# eurorack-passive-hpeq.net
KiCad netlist of a schematic drawn in EAGLE
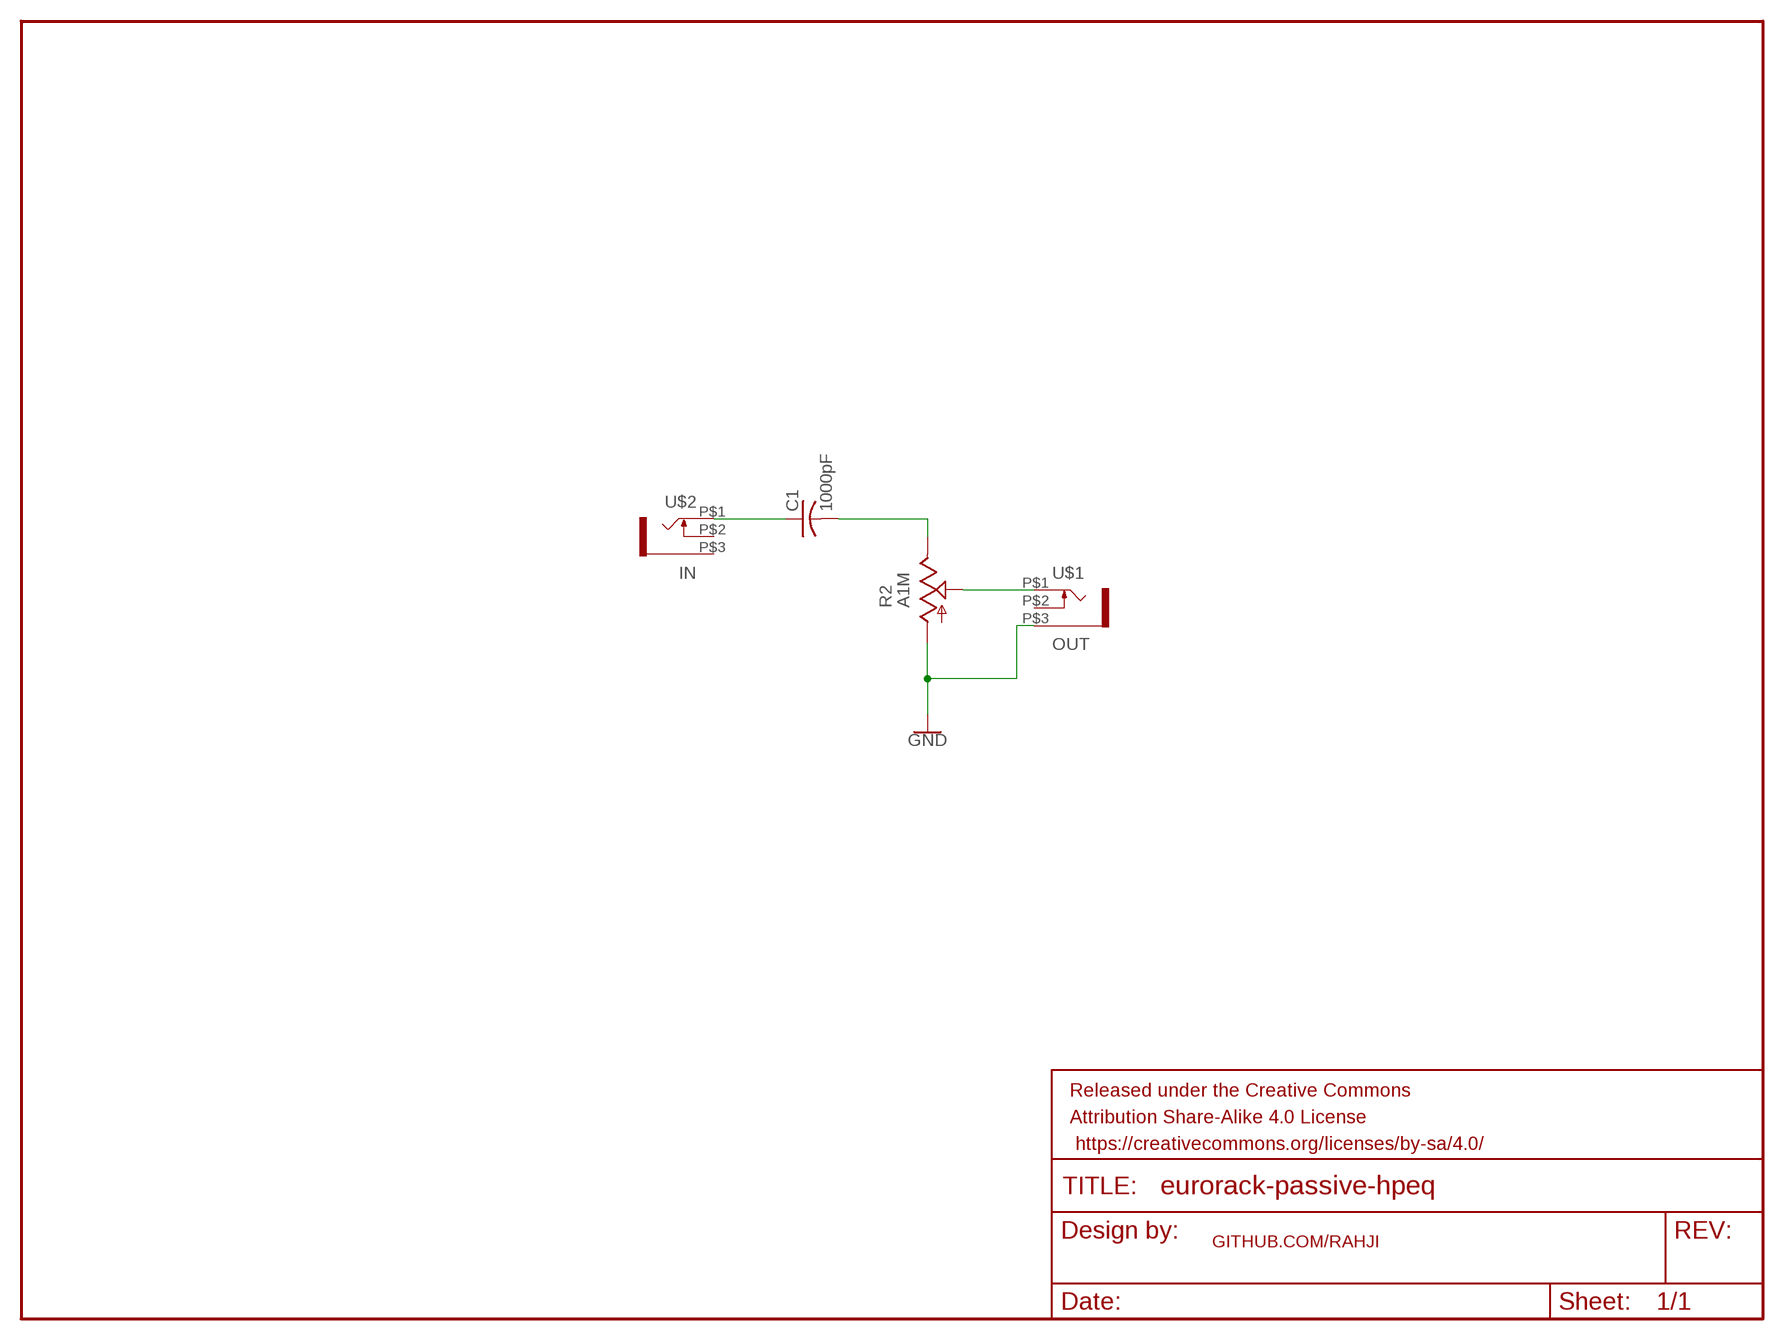
[diagram p0: schematic, sheet 1]

(export (version "E")
  (design (tool "Eeschema 10.0.6"))
  (components
    (comp (ref "C1")
      (value "1000pF")
      (footprint "eagle-import:C025-025X050")
      (libsource (lib "eagle-import") (part "C-US025-025X050"))
    )
    (comp (ref "FRAME1")
      (value "FRAME-LETTERNO_PACKAGE")
      (footprint "eagle-import:DUMMY")
      (fields (field (name "DESIGNER") "Nobody"))
      (libsource (lib "eagle-import") (part "FRAME-LETTERNO_PACKAGE"))
    )
    (comp (ref "R2")
      (value "A1M")
      (footprint "eagle-import:EVUF")
      (libsource (lib "eagle-import") (part "ALPHA-9MMAF3"))
    )
    (comp (ref "U$1")
      (value "OUT")
      (footprint "eagle-import:WQP-PJ301M-12_JACK")
      (libsource (lib "eagle-import") (part "WQP-PJ301M-12_JACK"))
    )
    (comp (ref "U$2")
      (value "IN")
      (footprint "eagle-import:WQP-PJ301M-12_JACK")
      (libsource (lib "eagle-import") (part "WQP-PJ301M-12_JACK"))
    )
  )
  (nets
    (net (code "1") (name "GND") (class "Default")
      (node (ref "R2") (pin "1") (pinfunction "A_1") (pintype "passive"))
      (node (ref "U$1") (pin "P$3") (pinfunction "1_P$3") (pintype "passive"))
    )
    (net (code "2") (name "Net-(R2-E)") (class "Default")
      (node (ref "C1") (pin "2") (pinfunction "2_2") (pintype "passive"))
      (node (ref "R2") (pin "3") (pinfunction "E_3") (pintype "passive"))
    )
    (net (code "3") (name "Net-(R2-S)") (class "Default")
      (node (ref "R2") (pin "2") (pinfunction "S_2") (pintype "passive"))
      (node (ref "U$1") (pin "P$1") (pinfunction "2_P$1") (pintype "passive"))
    )
    (net (code "4") (name "Net-(U$2-2)") (class "Default")
      (node (ref "C1") (pin "1") (pinfunction "1_1") (pintype "passive"))
      (node (ref "U$2") (pin "P$1") (pinfunction "2_P$1") (pintype "passive"))
    )
    (net (code "5") (name "unconnected-(U$1-3-PadP$2)") (class "Default")
      (node (ref "U$1") (pin "P$2") (pinfunction "3_P$2") (pintype "passive"))
    )
    (net (code "6") (name "unconnected-(U$2-1-PadP$3)") (class "Default")
      (node (ref "U$2") (pin "P$3") (pinfunction "1_P$3") (pintype "passive"))
    )
    (net (code "7") (name "unconnected-(U$2-3-PadP$2)") (class "Default")
      (node (ref "U$2") (pin "P$2") (pinfunction "3_P$2") (pintype "passive"))
    )
  )
)
